# Sheet3_IR.net
KiCad netlist of a schematic drawn in Altium Designer
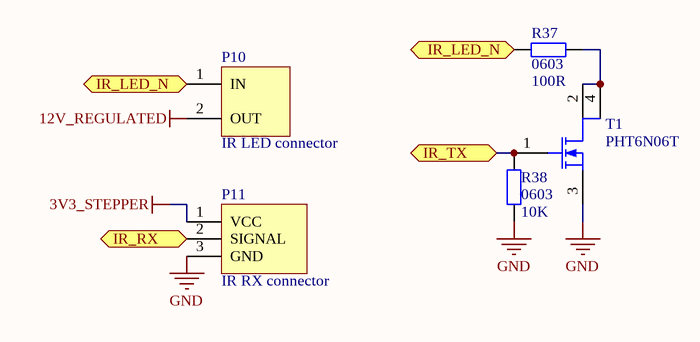
[diagram p0: Sheet3_IR.SchDoc]

(export (version "E")
  (design (tool "Eeschema 10.0.6"))
  (components
    (comp (ref "P10")
      (value "IR LED connector")
      (footprint "term_block_2_45mm")
      (libsource (lib "SchlibKoruzaExpanderBoard") (part "IR_LED_connector"))
    )
    (comp (ref "P11")
      (value "IR RX connector")
      (footprint "term_block_3pole_2_45mm")
      (libsource (lib "SchlibKoruzaExpanderBoard") (part "IR_RX_connector"))
    )
    (comp (ref "R37")
      (value "0603")
      (footprint "0603_HandSoldering")
      (description "Resistor")
      (fields (field (name "ALTIUM_VALUE") "100R"))
      (libsource (lib "") (part "resistor_1"))
    )
    (comp (ref "R38")
      (value "0603")
      (footprint "0603_HandSoldering")
      (description "Resistor")
      (fields (field (name "ALTIUM_VALUE") "10K"))
      (libsource (lib "SchlibKoruzaExpanderBoard") (part "resistor"))
    )
    (comp (ref "T1")
      (value "PHT6N06T")
      (footprint "SOT230P700X180-4N")
      (description "N MOSFET")
      (libsource (lib "SchlibKoruzaExpanderBoard") (part "PHT6N06T"))
    )
  )
  (nets
    (net (code "1") (name "/IR_LED_N") (class "Default")
      (node (ref "P10") (pin "1") (pinfunction "IN_1") (pintype "passive"))
      (node (ref "R37") (pin "2") (pinfunction "2_2") (pintype "passive"))
    )
    (net (code "2") (name "/IR_RX") (class "Default")
      (node (ref "P11") (pin "2") (pinfunction "SIGNAL_2") (pintype "passive"))
    )
    (net (code "3") (name "/IR_TX") (class "Default")
      (node (ref "R38") (pin "2") (pinfunction "2_2") (pintype "passive"))
      (node (ref "T1") (pin "1") (pinfunction "G_1") (pintype "passive"))
    )
    (net (code "4") (name "3V3_STEPPER") (class "Default")
      (node (ref "P11") (pin "1") (pinfunction "VCC_1") (pintype "passive"))
    )
    (net (code "5") (name "12V_REGULATED") (class "Default")
      (node (ref "P10") (pin "2") (pinfunction "OUT_2") (pintype "passive"))
    )
    (net (code "6") (name "GND") (class "Default")
      (node (ref "P11") (pin "3") (pinfunction "GND_3") (pintype "passive"))
      (node (ref "R38") (pin "1") (pinfunction "1_1") (pintype "passive"))
      (node (ref "T1") (pin "3") (pinfunction "S_3") (pintype "passive"))
    )
    (net (code "7") (name "Net-(R37-Pad1)") (class "Default")
      (node (ref "R37") (pin "1") (pinfunction "1_1") (pintype "passive"))
      (node (ref "T1") (pin "2") (pinfunction "D_2") (pintype "passive"))
      (node (ref "T1") (pin "4") (pinfunction "D_4") (pintype "passive"))
    )
  )
)
